# JTAG_ALTIUM_NANOTALK.net
KiCad netlist of a schematic drawn in Altium Designer
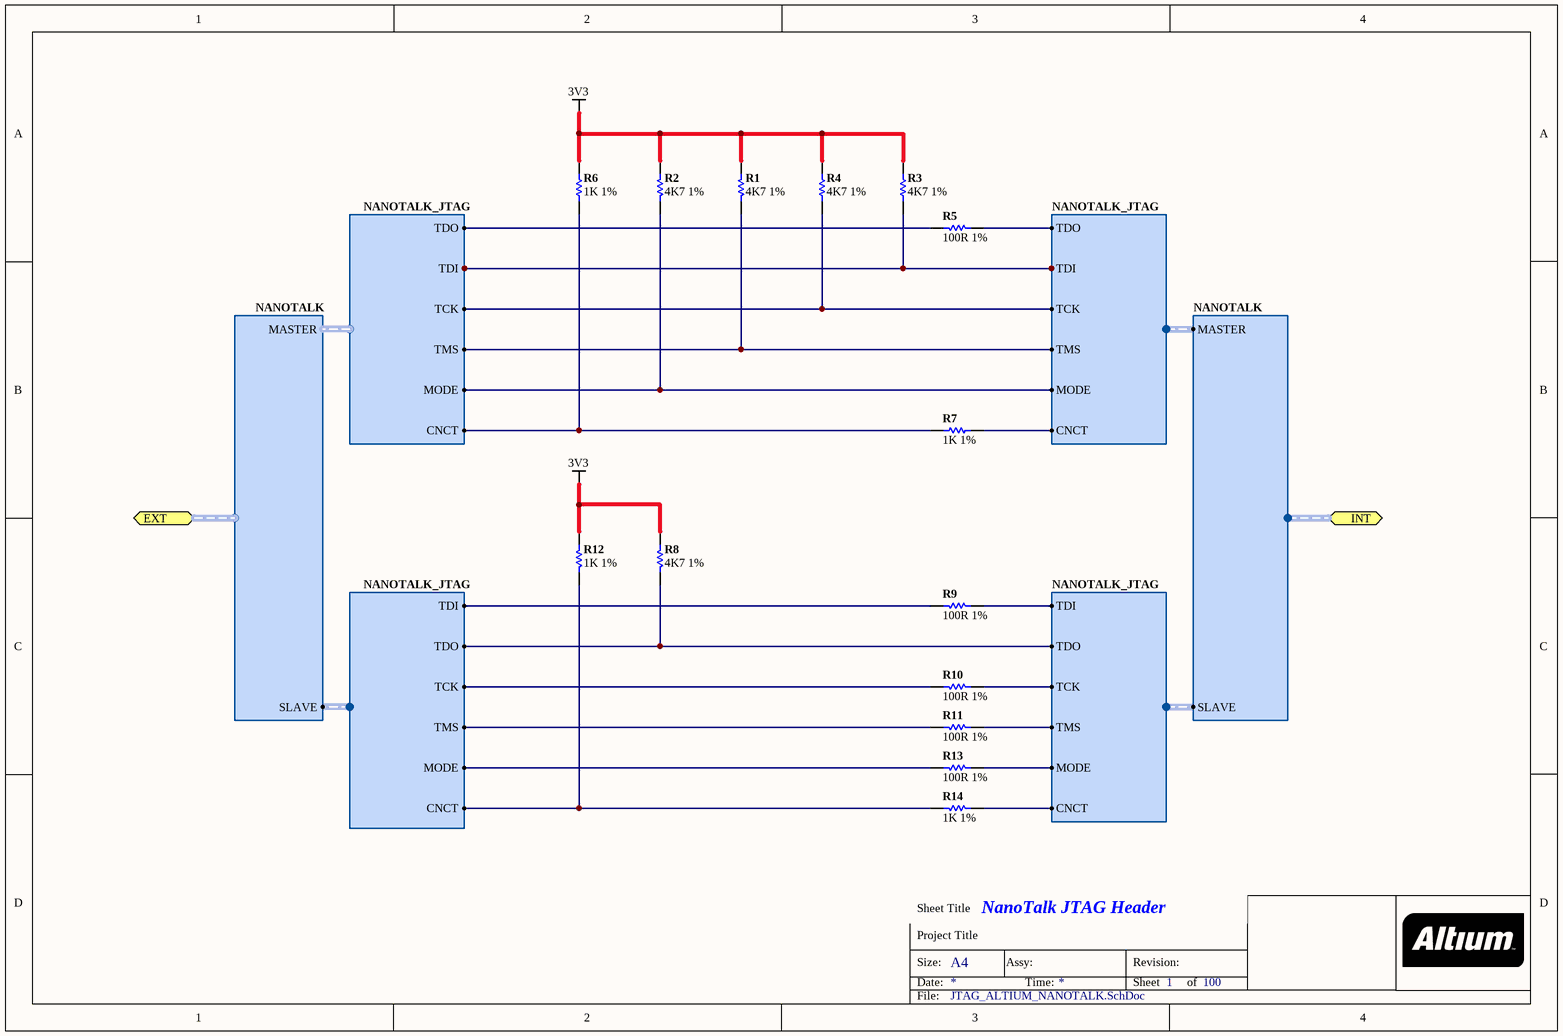
[diagram p0: JTAG_ALTIUM_NANOTALK.SchDoc]

(export (version "E")
  (design (tool "Eeschema 10.0.6"))
  (components
    (comp (ref "R1")
      (value "4K7 1%")
      (footprint "RESC1005-STAR")
      (description "Resistor, 4K7 1% 0402 (1005)")
      (fields (field (name "TOLERANCE") "1 %"))
      (libsource (lib "altium-import") (part "root_2_mirrored_RES_"))
    )
    (comp (ref "R2")
      (value "4K7 1%")
      (footprint "RESC1005-STAR")
      (description "Resistor, 4K7 1% 0402 (1005)")
      (fields (field (name "TOLERANCE") "1 %"))
      (libsource (lib "altium-import") (part "root_2_mirrored_RES_"))
    )
    (comp (ref "R3")
      (value "4K7 1%")
      (footprint "RESC1005-STAR")
      (description "Resistor, 4K7 1% 0402 (1005)")
      (fields (field (name "TOLERANCE") "1 %"))
      (libsource (lib "altium-import") (part "root_2_RES_"))
    )
    (comp (ref "R4")
      (value "4K7 1%")
      (footprint "RESC1005-STAR")
      (description "Resistor, 4K7 1% 0402 (1005)")
      (fields (field (name "TOLERANCE") "1 %"))
      (libsource (lib "altium-import") (part "root_2_RES_"))
    )
    (comp (ref "R5")
      (value "100R 1%")
      (footprint "RESC1005-STAR")
      (description "Resistor, 100R 1% 0402 (1005)")
      (fields (field (name "TOLERANCE") "1 %"))
      (libsource (lib "altium-import") (part "root_3_mirrored_RES_"))
    )
    (comp (ref "R6")
      (value "1K 1%")
      (footprint "RESC1005-STAR")
      (description "Resistor, 1K 1% 0402 (1005)")
      (fields (field (name "TOLERANCE") "1 %"))
      (libsource (lib "altium-import") (part "root_0_RES_"))
    )
    (comp (ref "R7")
      (value "1K 1%")
      (footprint "RESC1005-STAR")
      (description "Resistor, 1K 1% 0402 (1005)")
      (fields (field (name "TOLERANCE") "1 %"))
      (libsource (lib "altium-import") (part "root_1_RES_"))
    )
    (comp (ref "R8")
      (value "4K7 1%")
      (footprint "RESC1005-STAR")
      (description "Resistor, 4K7 1% 0402 (1005)")
      (fields (field (name "TOLERANCE") "1 %"))
      (libsource (lib "altium-import") (part "root_0_mirrored_RES_"))
    )
    (comp (ref "R9")
      (value "100R 1%")
      (footprint "RESC1005-STAR")
      (description "Resistor, 100R 1% 0402 (1005)")
      (fields (field (name "TOLERANCE") "1 %"))
      (libsource (lib "altium-import") (part "root_3_mirrored_RES_"))
    )
    (comp (ref "R10")
      (value "100R 1%")
      (footprint "RESC1005-STAR")
      (description "Resistor, 100R 1% 0402 (1005)")
      (fields (field (name "TOLERANCE") "1 %"))
      (libsource (lib "altium-import") (part "root_3_mirrored_RES_"))
    )
    (comp (ref "R11")
      (value "100R 1%")
      (footprint "RESC1005-STAR")
      (description "Resistor, 100R 1% 0402 (1005)")
      (fields (field (name "TOLERANCE") "1 %"))
      (libsource (lib "altium-import") (part "root_1_mirrored_RES_"))
    )
    (comp (ref "R12")
      (value "1K 1%")
      (footprint "RESC1005-STAR")
      (description "Resistor, 1K 1% 0402 (1005)")
      (fields (field (name "TOLERANCE") "1 %"))
      (libsource (lib "altium-import") (part "root_0_mirrored_RES_"))
    )
    (comp (ref "R13")
      (value "100R 1%")
      (footprint "RESC1005-STAR")
      (description "Resistor, 100R 1% 0402 (1005)")
      (fields (field (name "TOLERANCE") "1 %"))
      (libsource (lib "altium-import") (part "root_1_mirrored_RES_"))
    )
    (comp (ref "R14")
      (value "1K 1%")
      (footprint "RESC1005-STAR")
      (description "Resistor, 1K 1% 0402 (1005)")
      (fields (field (name "TOLERANCE") "1 %"))
      (libsource (lib "altium-import") (part "root_3_mirrored_RES_"))
    )
  )
  (nets
    (net (code "9") (name "3V3") (class "Default")
      (node (ref "R1") (pin "2") (pinfunction "2_2") (pintype "passive"))
      (node (ref "R12") (pin "1") (pinfunction "1_1") (pintype "passive"))
      (node (ref "R2") (pin "2") (pinfunction "2_2") (pintype "passive"))
      (node (ref "R3") (pin "2") (pinfunction "2_2") (pintype "passive"))
      (node (ref "R4") (pin "2") (pinfunction "2_2") (pintype "passive"))
      (node (ref "R6") (pin "1") (pinfunction "1_1") (pintype "passive"))
      (node (ref "R8") (pin "1") (pinfunction "1_1") (pintype "passive"))
    )
    (net (code "10") (name "Net-(R6-Pad2)") (class "Default")
      (node (ref "R6") (pin "2") (pinfunction "2_2") (pintype "passive"))
      (node (ref "R7") (pin "1") (pinfunction "1_1") (pintype "passive"))
    )
    (net (code "11") (name "Net-(R12-Pad2)") (class "Default")
      (node (ref "R12") (pin "2") (pinfunction "2_2") (pintype "passive"))
      (node (ref "R14") (pin "1") (pinfunction "1_1") (pintype "passive"))
    )
    (net (code "12") (name "unconnected-(R1-Pad1)") (class "Default")
      (node (ref "R1") (pin "1") (pinfunction "1_1") (pintype "passive"))
    )
    (net (code "13") (name "unconnected-(R2-Pad1)") (class "Default")
      (node (ref "R2") (pin "1") (pinfunction "1_1") (pintype "passive"))
    )
    (net (code "14") (name "unconnected-(R3-Pad1)") (class "Default")
      (node (ref "R3") (pin "1") (pinfunction "1_1") (pintype "passive"))
    )
    (net (code "15") (name "unconnected-(R4-Pad1)") (class "Default")
      (node (ref "R4") (pin "1") (pinfunction "1_1") (pintype "passive"))
    )
    (net (code "16") (name "unconnected-(R5-Pad1)") (class "Default")
      (node (ref "R5") (pin "1") (pinfunction "1_1") (pintype "passive"))
    )
    (net (code "17") (name "unconnected-(R5-Pad2)") (class "Default")
      (node (ref "R5") (pin "2") (pinfunction "2_2") (pintype "passive"))
    )
    (net (code "18") (name "unconnected-(R7-Pad2)") (class "Default")
      (node (ref "R7") (pin "2") (pinfunction "2_2") (pintype "passive"))
    )
    (net (code "19") (name "unconnected-(R8-Pad2)") (class "Default")
      (node (ref "R8") (pin "2") (pinfunction "2_2") (pintype "passive"))
    )
    (net (code "20") (name "unconnected-(R9-Pad1)") (class "Default")
      (node (ref "R9") (pin "1") (pinfunction "1_1") (pintype "passive"))
    )
    (net (code "21") (name "unconnected-(R9-Pad2)") (class "Default")
      (node (ref "R9") (pin "2") (pinfunction "2_2") (pintype "passive"))
    )
    (net (code "22") (name "unconnected-(R10-Pad1)") (class "Default")
      (node (ref "R10") (pin "1") (pinfunction "1_1") (pintype "passive"))
    )
    (net (code "23") (name "unconnected-(R10-Pad2)") (class "Default")
      (node (ref "R10") (pin "2") (pinfunction "2_2") (pintype "passive"))
    )
    (net (code "24") (name "unconnected-(R11-Pad1)") (class "Default")
      (node (ref "R11") (pin "1") (pinfunction "1_1") (pintype "passive"))
    )
    (net (code "25") (name "unconnected-(R11-Pad2)") (class "Default")
      (node (ref "R11") (pin "2") (pinfunction "2_2") (pintype "passive"))
    )
    (net (code "26") (name "unconnected-(R13-Pad1)") (class "Default")
      (node (ref "R13") (pin "1") (pinfunction "1_1") (pintype "passive"))
    )
    (net (code "27") (name "unconnected-(R13-Pad2)") (class "Default")
      (node (ref "R13") (pin "2") (pinfunction "2_2") (pintype "passive"))
    )
    (net (code "28") (name "unconnected-(R14-Pad2)") (class "Default")
      (node (ref "R14") (pin "2") (pinfunction "2_2") (pintype "passive"))
    )
  )
)
